# 4PDTrelay_w_diodes.net
KiCad netlist of a schematic drawn in EAGLE
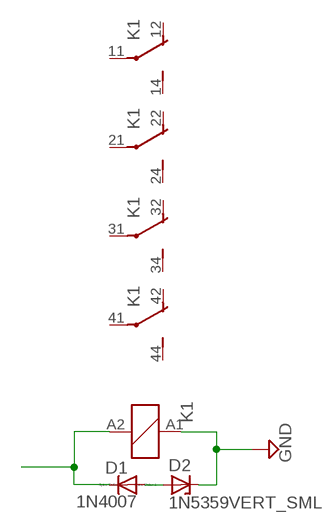
[diagram p0: schematic, sheet 1]

(export (version "E")
  (design (tool "Eeschema 10.0.6"))
  (components
    (comp (ref "D1")
      (value "1N4007")
      (footprint "eagle-import:RAD2,5")
      (libsource (lib "eagle-import") (part "1N4007"))
    )
    (comp (ref "D2")
      (value "1N5359VERT_SML")
      (footprint "eagle-import:RAD2.5_D2")
      (libsource (lib "eagle-import") (part "1N5359VERT_SML"))
    )
    (comp (ref "K1")
      (value "PY14-02")
      (footprint "eagle-import:PY14-02")
      (libsource (lib "eagle-import") (part "PY14-02"))
    )
  )
  (nets
    (net (code "1") (name "GND") (class "Default")
      (node (ref "D2") (pin "C") (pinfunction "C_C") (pintype "passive"))
      (node (ref "K1") (pin "A1") (pinfunction "1_A1") (pintype "passive"))
    )
    (net (code "2") (name "Net-(D1-PadA)") (class "Default")
      (node (ref "D1") (pin "A") (pinfunction "A_A") (pintype "passive"))
      (node (ref "D2") (pin "A") (pinfunction "A_A") (pintype "passive"))
    )
    (net (code "3") (name "Net-(K1A-2)") (class "Default")
      (node (ref "D1") (pin "C") (pinfunction "C_C") (pintype "passive"))
      (node (ref "K1") (pin "A2") (pinfunction "2_A2") (pintype "passive"))
    )
    (net (code "4") (name "unconnected-(K1B-O-Pad12)") (class "Default")
      (node (ref "K1") (pin "12") (pinfunction "O_12") (pintype "passive"))
    )
    (net (code "5") (name "unconnected-(K1B-P-Pad11)") (class "Default")
      (node (ref "K1") (pin "11") (pinfunction "P_11") (pintype "passive"))
    )
    (net (code "6") (name "unconnected-(K1B-S-Pad14)") (class "Default")
      (node (ref "K1") (pin "14") (pinfunction "S_14") (pintype "passive"))
    )
    (net (code "7") (name "unconnected-(K1C-O-Pad22)") (class "Default")
      (node (ref "K1") (pin "22") (pinfunction "O_22") (pintype "passive"))
    )
    (net (code "8") (name "unconnected-(K1C-P-Pad21)") (class "Default")
      (node (ref "K1") (pin "21") (pinfunction "P_21") (pintype "passive"))
    )
    (net (code "9") (name "unconnected-(K1C-S-Pad24)") (class "Default")
      (node (ref "K1") (pin "24") (pinfunction "S_24") (pintype "passive"))
    )
    (net (code "10") (name "unconnected-(K1D-O-Pad32)") (class "Default")
      (node (ref "K1") (pin "32") (pinfunction "O_32") (pintype "passive"))
    )
    (net (code "11") (name "unconnected-(K1D-P-Pad31)") (class "Default")
      (node (ref "K1") (pin "31") (pinfunction "P_31") (pintype "passive"))
    )
    (net (code "12") (name "unconnected-(K1D-S-Pad34)") (class "Default")
      (node (ref "K1") (pin "34") (pinfunction "S_34") (pintype "passive"))
    )
    (net (code "13") (name "unconnected-(K1E-O-Pad42)") (class "Default")
      (node (ref "K1") (pin "42") (pinfunction "O_42") (pintype "passive"))
    )
    (net (code "14") (name "unconnected-(K1E-P-Pad41)") (class "Default")
      (node (ref "K1") (pin "41") (pinfunction "P_41") (pintype "passive"))
    )
    (net (code "15") (name "unconnected-(K1E-S-Pad44)") (class "Default")
      (node (ref "K1") (pin "44") (pinfunction "S_44") (pintype "passive"))
    )
  )
)
